# dimmer_encoder_controller.net
KiCad netlist of a schematic drawn in EAGLE
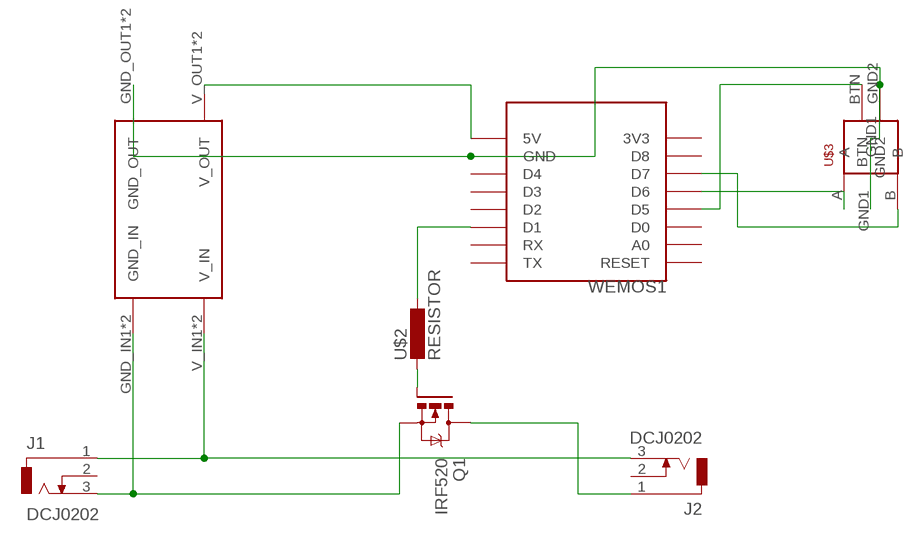
[diagram p0: schematic, sheet 1]

(export (version "E")
  (design (tool "Eeschema 10.0.6"))
  (components
    (comp (ref "J1")
      (value "DCJ0202")
      (footprint "eagle-import:DCJ0202")
      (libsource (lib "eagle-import") (part "DCJ0202"))
    )
    (comp (ref "J2")
      (value "DCJ0202")
      (footprint "eagle-import:DCJ0202")
      (libsource (lib "eagle-import") (part "DCJ0202"))
    )
    (comp (ref "Q1")
      (value "IRF520")
      (footprint "eagle-import:TO220BV")
      (libsource (lib "eagle-import") (part "IRF520"))
    )
    (comp (ref "U$1")
      (value "DC-DC-CONVERTER")
      (footprint "eagle-import:DC-DC-CONVERTER")
      (libsource (lib "eagle-import") (part "DC-DC-CONVERTER"))
    )
    (comp (ref "U$2")
      (value "RESISTOR")
      (footprint "eagle-import:RESISTOR")
      (libsource (lib "eagle-import") (part "RESISTOR"))
    )
    (comp (ref "U$3")
      (value "ROTARY_ENCODER")
      (footprint "eagle-import:ROTARY_ENCODER")
      (libsource (lib "eagle-import") (part "ROTARY_ENCODER"))
    )
    (comp (ref "WEMOS1")
      (value "WEMOS-D1-MINI")
      (footprint "eagle-import:WEMOS-D1-MINI")
      (libsource (lib "eagle-import") (part "WEMOS-D1-MINI"))
    )
  )
  (nets
    (net (code "1") (name "Net-(J1-Pad1)") (class "Default")
      (node (ref "J1") (pin "1") (pinfunction "1_1") (pintype "passive"))
      (node (ref "J2") (pin "3") (pinfunction "3_3") (pintype "passive"))
      (node (ref "U$1") (pin "V_IN1") (pinfunction "V_IN_V_IN1") (pintype "bidirectional"))
      (node (ref "U$1") (pin "V_IN2") (pinfunction "V_IN_V_IN2") (pintype "bidirectional"))
    )
    (net (code "2") (name "Net-(J1-Pad3)") (class "Default")
      (node (ref "J1") (pin "3") (pinfunction "3_3") (pintype "passive"))
      (node (ref "Q1") (pin "S") (pinfunction "S_S") (pintype "passive"))
      (node (ref "U$1") (pin "GND_IN1") (pinfunction "GND_IN_GND_IN1") (pintype "bidirectional"))
      (node (ref "U$1") (pin "GND_IN2") (pinfunction "GND_IN_GND_IN2") (pintype "bidirectional"))
    )
    (net (code "3") (name "Net-(J2-Pad1)") (class "Default")
      (node (ref "J2") (pin "1") (pinfunction "1_1") (pintype "passive"))
      (node (ref "Q1") (pin "D") (pinfunction "D_D") (pintype "passive"))
    )
    (net (code "4") (name "Net-(Q1-PadG)") (class "Default")
      (node (ref "Q1") (pin "G") (pinfunction "G_G") (pintype "passive"))
      (node (ref "U$2") (pin "2") (pinfunction "2_2") (pintype "passive"))
    )
    (net (code "5") (name "Net-(U$1-GND_OUT-PadGND_OUT1)") (class "Default")
      (node (ref "U$1") (pin "GND_OUT1") (pinfunction "GND_OUT_GND_OUT1") (pintype "bidirectional"))
      (node (ref "U$1") (pin "GND_OUT2") (pinfunction "GND_OUT_GND_OUT2") (pintype "bidirectional"))
      (node (ref "U$3") (pin "GND1") (pinfunction "GND1_GND1") (pintype "bidirectional"))
      (node (ref "U$3") (pin "GND2") (pinfunction "GND2_GND2") (pintype "bidirectional"))
      (node (ref "WEMOS1") (pin "GND") (pinfunction "GND_GND") (pintype "bidirectional"))
    )
    (net (code "6") (name "Net-(U$1-V_OUT-PadV_OUT1)") (class "Default")
      (node (ref "U$1") (pin "V_OUT1") (pinfunction "V_OUT_V_OUT1") (pintype "bidirectional"))
      (node (ref "U$1") (pin "V_OUT2") (pinfunction "V_OUT_V_OUT2") (pintype "bidirectional"))
      (node (ref "WEMOS1") (pin "5V") (pinfunction "5V_5V") (pintype "bidirectional"))
    )
    (net (code "7") (name "Net-(U$2-Pad1)") (class "Default")
      (node (ref "U$2") (pin "1") (pinfunction "1_1") (pintype "passive"))
      (node (ref "WEMOS1") (pin "D1") (pinfunction "D1_D1") (pintype "bidirectional"))
    )
    (net (code "8") (name "Net-(U$3-PadA)") (class "Default")
      (node (ref "U$3") (pin "A") (pinfunction "A_A") (pintype "bidirectional"))
      (node (ref "WEMOS1") (pin "D6") (pinfunction "D6_D6") (pintype "bidirectional"))
    )
    (net (code "9") (name "Net-(U$3-PadB)") (class "Default")
      (node (ref "U$3") (pin "B") (pinfunction "B_B") (pintype "bidirectional"))
      (node (ref "WEMOS1") (pin "D7") (pinfunction "D7_D7") (pintype "bidirectional"))
    )
    (net (code "10") (name "Net-(U$3-PadBTN)") (class "Default")
      (node (ref "U$3") (pin "BTN") (pinfunction "BTN_BTN") (pintype "bidirectional"))
      (node (ref "WEMOS1") (pin "D5") (pinfunction "D5_D5") (pintype "bidirectional"))
    )
    (net (code "11") (name "unconnected-(J1-Pad2)") (class "Default")
      (node (ref "J1") (pin "2") (pinfunction "2_2") (pintype "passive"))
    )
    (net (code "12") (name "unconnected-(J2-Pad2)") (class "Default")
      (node (ref "J2") (pin "2") (pinfunction "2_2") (pintype "passive"))
    )
    (net (code "13") (name "unconnected-(WEMOS1-Pad3V3)") (class "Default")
      (node (ref "WEMOS1") (pin "3V3") (pinfunction "3V3_3V3") (pintype "bidirectional"))
    )
    (net (code "14") (name "unconnected-(WEMOS1-PadA0)") (class "Default")
      (node (ref "WEMOS1") (pin "A0") (pinfunction "A0_A0") (pintype "bidirectional"))
    )
    (net (code "15") (name "unconnected-(WEMOS1-PadD0)") (class "Default")
      (node (ref "WEMOS1") (pin "D0") (pinfunction "D0_D0") (pintype "bidirectional"))
    )
    (net (code "16") (name "unconnected-(WEMOS1-PadD2)") (class "Default")
      (node (ref "WEMOS1") (pin "D2") (pinfunction "D2_D2") (pintype "bidirectional"))
    )
    (net (code "17") (name "unconnected-(WEMOS1-PadD3)") (class "Default")
      (node (ref "WEMOS1") (pin "D3") (pinfunction "D3_D3") (pintype "bidirectional"))
    )
    (net (code "18") (name "unconnected-(WEMOS1-PadD4)") (class "Default")
      (node (ref "WEMOS1") (pin "D4") (pinfunction "D4_D4") (pintype "bidirectional"))
    )
    (net (code "19") (name "unconnected-(WEMOS1-PadD8)") (class "Default")
      (node (ref "WEMOS1") (pin "D8") (pinfunction "D8_D8") (pintype "bidirectional"))
    )
    (net (code "20") (name "unconnected-(WEMOS1-PadRESET)") (class "Default")
      (node (ref "WEMOS1") (pin "RESET") (pinfunction "RESET_RESET") (pintype "bidirectional"))
    )
    (net (code "21") (name "unconnected-(WEMOS1-PadRX)") (class "Default")
      (node (ref "WEMOS1") (pin "RX") (pinfunction "RX_RX") (pintype "bidirectional"))
    )
    (net (code "22") (name "unconnected-(WEMOS1-PadTX)") (class "Default")
      (node (ref "WEMOS1") (pin "TX") (pinfunction "TX_TX") (pintype "bidirectional"))
    )
  )
)
